# 1_P1.net
KiCad netlist of a schematic drawn in Altium Designer
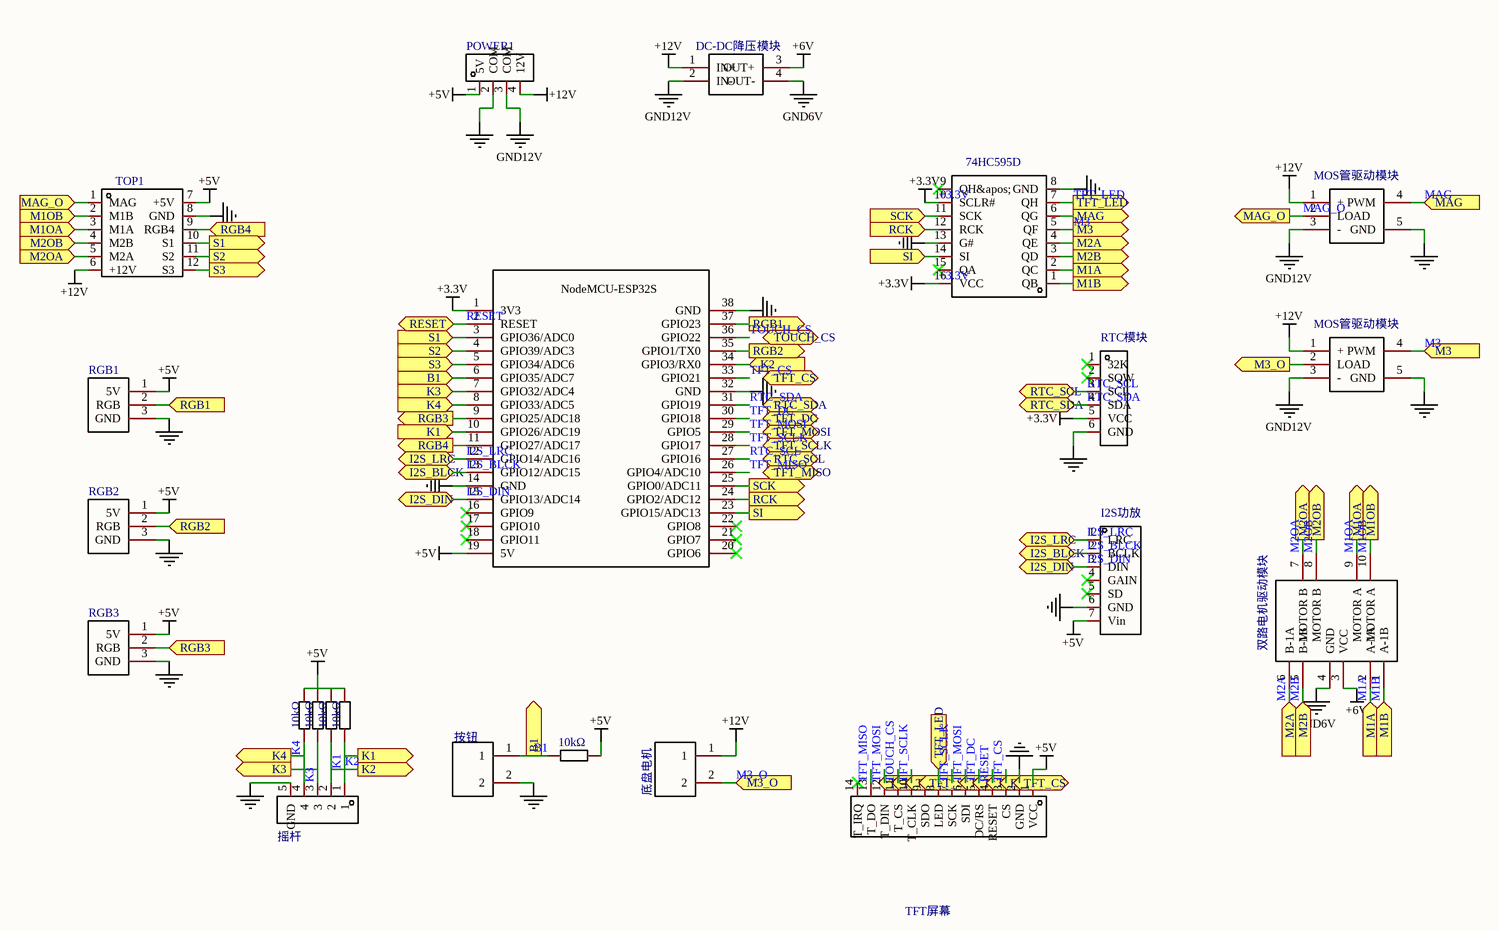
[diagram p0: 1_P1.schdoc]

(export (version "E")
  (design (tool "Eeschema 10.0.6"))
  (components
    (comp (ref "B1")
      (value "按钮")
      (description "系列:PH;连接器类型:接头;触头类型:公形引脚;间距:0.079")
      (fields
        (field (name "NAME") "按钮")
        (field (name "MANUFACTURER") "BOOMELE(博穆精密)")
        (field (name "MANUFACTURER PART") "PH-2A")
      )
      (libsource (lib "altium-import") (part "root_1_按钮_"))
    )
    (comp (ref "H2")
      (value "I2S功放")
      (description "间距:2.54mm;行距:-;触头镀层:-;触头材质:黄铜;安装类型:直插;塑高:-;总孔位数:7;排数:1;")
      (fields
        (field (name "DEVICE") "I2S功放")
        (field (name "MANUFACTURER") "Ckmtw(灿科盟)")
        (field (name "MANUFACTURER PART") "B-2200S07P-A120")
      )
      (libsource (lib "altium-import") (part "root_0_I2S功放_"))
    )
    (comp (ref "KEYPAD1")
      (value "摇杆")
      (description "系列:PH;连接器类型:接头;触头类型:公形引脚;间距:0.079")
      (fields
        (field (name "DEVICE") "摇杆")
        (field (name "MANUFACTURER") "BOOMELE(博穆精密)")
        (field (name "MANUFACTURER PART") "PH-5A")
      )
      (libsource (lib "altium-import") (part "root_3_摇杆_"))
    )
    (comp (ref "M3")
      (value "底盘电机")
      (description "系列:PH;连接器类型:接头;触头类型:公形引脚;间距:0.079")
      (fields
        (field (name "NAME") "底盘电机")
        (field (name "MANUFACTURER") "BOOMELE(博穆精密)")
        (field (name "MANUFACTURER PART") "PH-2A")
      )
      (libsource (lib "altium-import") (part "root_1_按钮_"))
    )
    (comp (ref "P5")
      (value "RTC模块")
      (description "间距:2.54mm;行距:-;触头镀层:-;触头材质:-;安装类型:直插;塑高:-;总孔位数:6;排数:1;")
      (fields
        (field (name "DEVICE") "RTC模块")
        (field (name "MANUFACTURER") "BOOMELE(博穆精密)")
        (field (name "MANUFACTURER PART") "2.54-1*6P母")
      )
      (libsource (lib "altium-import") (part "root_0_RTC模块_"))
    )
    (comp (ref "POWER1")
      (value "开关电源接线柱")
      (fields
        (field (name "MANUFACTURER") "DIBO(地博电子)")
        (field (name "MANUFACTURER PART") "DB125-3.81-4P-GN")
      )
      (libsource (lib "altium-import") (part "root_1_开关电源接线柱_"))
    )
    (comp (ref "R1")
      (value "10kΩ")
      (description "精度:±1%;温度系数:±100ppm/℃;阻值:10kΩ;功率:100mW;最大工作电压:75V;工作温度范围:-55℃~+155℃;")
      (fields (field (name "MANUFACTURER") "YAGEO(国巨)") (field (name "MANUFACTURER PART") "RC0603FR-0710KL"))
      (libsource (lib "altium-import") (part "root_1_RC0603FR-0710KL_"))
    )
    (comp (ref "R2")
      (value "10kΩ")
      (description "精度:±1%;温度系数:±100ppm/℃;阻值:10kΩ;功率:100mW;最大工作电压:75V;工作温度范围:-55℃~+155℃;")
      (fields (field (name "MANUFACTURER") "YAGEO(国巨)") (field (name "MANUFACTURER PART") "RC0603FR-0710KL"))
      (libsource (lib "altium-import") (part "root_1_RC0603FR-0710KL_"))
    )
    (comp (ref "R3")
      (value "10kΩ")
      (description "精度:±1%;温度系数:±100ppm/℃;阻值:10kΩ;功率:100mW;最大工作电压:75V;工作温度范围:-55℃~+155℃;")
      (fields (field (name "MANUFACTURER") "YAGEO(国巨)") (field (name "MANUFACTURER PART") "RC0603FR-0710KL"))
      (libsource (lib "altium-import") (part "root_1_RC0603FR-0710KL_"))
    )
    (comp (ref "R4")
      (value "10kΩ")
      (description "精度:±1%;温度系数:±100ppm/℃;阻值:10kΩ;功率:100mW;最大工作电压:75V;工作温度范围:-55℃~+155℃;")
      (fields (field (name "MANUFACTURER") "YAGEO(国巨)") (field (name "MANUFACTURER PART") "RC0603FR-0710KL"))
      (libsource (lib "altium-import") (part "root_1_RC0603FR-0710KL_"))
    )
    (comp (ref "R5")
      (value "10kΩ")
      (description "精度:±1%;温度系数:±100ppm/℃;阻值:10kΩ;功率:100mW;最大工作电压:75V;工作温度范围:-55℃~+155℃;")
      (fields (field (name "MANUFACTURER") "YAGEO(国巨)") (field (name "MANUFACTURER PART") "RC0603FR-0710KL"))
      (libsource (lib "altium-import") (part "root_0_RC0603FR-0710KL_"))
    )
    (comp (ref "RGB1")
      (value "RGB1")
      (description "系列:PH;连接器类型:接头;触头类型:公形引脚;间距:0.079")
      (fields
        (field (name "NAME") "RGB1")
        (field (name "MANUFACTURER") "BOOMELE(博穆精密)")
        (field (name "MANUFACTURER PART") "PH-3A")
      )
      (libsource (lib "altium-import") (part "root_0_RGB_"))
    )
    (comp (ref "RGB2")
      (value "RGB2")
      (description "系列:PH;连接器类型:接头;触头类型:公形引脚;间距:0.079")
      (fields
        (field (name "NAME") "RGB2")
        (field (name "MANUFACTURER") "BOOMELE(博穆精密)")
        (field (name "MANUFACTURER PART") "PH-3A")
      )
      (libsource (lib "altium-import") (part "root_0_RGB_"))
    )
    (comp (ref "RGB3")
      (value "RGB3")
      (description "系列:PH;连接器类型:接头;触头类型:公形引脚;间距:0.079")
      (fields
        (field (name "NAME") "RGB3")
        (field (name "MANUFACTURER") "BOOMELE(博穆精密)")
        (field (name "MANUFACTURER PART") "PH-3A")
      )
      (libsource (lib "altium-import") (part "root_0_RGB_"))
    )
    (comp (ref "SCREEN1")
      (value "TFT屏幕")
      (fields
        (field (name "DEVICE") "TFT屏幕")
        (field (name "MANUFACTURER") "kinghelm(金航标)")
        (field (name "MANUFACTURER PART") "KH-A2541WV-14P")
      )
      (libsource (lib "altium-import") (part "root_3_TFT屏幕_"))
    )
    (comp (ref "TOP1")
      (value "顶盖")
      (description "系列:PHD;连接器类型:接头;触头类型:公形引脚;间距:0.079")
      (fields (field (name "MANUFACTURER") "BOOMELE(博穆精密)") (field (name "MANUFACTURER PART") "PHD-2*6A"))
      (libsource (lib "altium-import") (part "root_0_顶盖_"))
    )
    (comp (ref "U1") (value "NodeMCU-32S") (libsource (lib "altium-import") (part "root_0_NodeMCU-32S_")))
    (comp (ref "U15")
      (value "74HC595D")
      (description "输出类型:-;元件数:-;每元件位数:-;逻辑电路的归属系列:-;逻辑类型:-;")
      (fields (field (name "DEVICE") "74HC595D") (field (name "MANUFACTURER") "TOSHIBA(东芝)"))
      (libsource (lib "altium-import") (part "root_2_74HC595D_"))
    )
    (comp (ref "U16")
      (value "双路电机驱动模块")
      (fields (field (name "DEVICE") "双路电机驱动模块"))
      (libsource (lib "altium-import") (part "root_1_双路电机驱动模块_"))
    )
    (comp (ref "U17")
      (value "DC-DC降压模块")
      (fields (field (name "SYMBOL") "DC-DC降压模块"))
      (libsource (lib "altium-import") (part "root_0_DC-DC降压模块_"))
    )
    (comp (ref "U18")
      (value "MOS管驱动模块")
      (fields (field (name "DEVICE") "MOS管驱动模块"))
      (libsource (lib "altium-import") (part "root_0_MOS管驱动模块_"))
    )
    (comp (ref "U19")
      (value "MOS管驱动模块")
      (fields (field (name "DEVICE") "MOS管驱动模块"))
      (libsource (lib "altium-import") (part "root_0_MOS管驱动模块_"))
    )
  )
  (nets
    (net (code "1") (name "+3.3V") (class "Default")
      (node (ref "P5") (pin "5") (pinfunction "VCC_5") (pintype "passive"))
      (node (ref "U1") (pin "1") (pinfunction "3V3_1") (pintype "passive"))
      (node (ref "U15") (pin "10") (pinfunction "SCLR#_10") (pintype "passive"))
      (node (ref "U15") (pin "16") (pinfunction "VCC_16") (pintype "passive"))
    )
    (net (code "2") (name "+5V") (class "Default")
      (node (ref "H2") (pin "7") (pinfunction "Vin_7") (pintype "passive"))
      (node (ref "POWER1") (pin "1") (pinfunction "5V_1") (pintype "passive"))
      (node (ref "R1") (pin "2") (pinfunction "2_2") (pintype "passive"))
      (node (ref "R2") (pin "2") (pinfunction "2_2") (pintype "passive"))
      (node (ref "R3") (pin "2") (pinfunction "2_2") (pintype "passive"))
      (node (ref "R4") (pin "2") (pinfunction "2_2") (pintype "passive"))
      (node (ref "R5") (pin "2") (pinfunction "2_2") (pintype "passive"))
      (node (ref "RGB1") (pin "1") (pinfunction "5V_1") (pintype "passive"))
      (node (ref "RGB2") (pin "1") (pinfunction "5V_1") (pintype "passive"))
      (node (ref "RGB3") (pin "1") (pinfunction "5V_1") (pintype "passive"))
      (node (ref "SCREEN1") (pin "1") (pinfunction "VCC_1") (pintype "passive"))
      (node (ref "TOP1") (pin "7") (pinfunction "+5V_7") (pintype "passive"))
      (node (ref "U1") (pin "19") (pinfunction "5V_19") (pintype "passive"))
    )
    (net (code "3") (name "+6V") (class "Default")
      (node (ref "U16") (pin "3") (pinfunction "VCC_3") (pintype "passive"))
      (node (ref "U17") (pin "3") (pinfunction "OUT+_3") (pintype "passive"))
    )
    (net (code "4") (name "+12V") (class "Default")
      (node (ref "M3") (pin "1") (pinfunction "1_1") (pintype "passive"))
      (node (ref "POWER1") (pin "4") (pinfunction "12V_4") (pintype "passive"))
      (node (ref "TOP1") (pin "6") (pinfunction "+12V_6") (pintype "passive"))
      (node (ref "U17") (pin "1") (pinfunction "IN+_1") (pintype "passive"))
      (node (ref "U18") (pin "1") (pinfunction "+_1") (pintype "passive"))
      (node (ref "U19") (pin "1") (pinfunction "+_1") (pintype "passive"))
    )
    (net (code "5") (name "/B1") (class "Default")
      (node (ref "B1") (pin "1") (pinfunction "1_1") (pintype "passive"))
      (node (ref "R5") (pin "1") (pinfunction "1_1") (pintype "passive"))
      (node (ref "U1") (pin "6") (pinfunction "GPIO35/ADC7_6") (pintype "passive"))
    )
    (net (code "6") (name "/I2S_BLCK") (class "Default")
      (node (ref "H2") (pin "2") (pinfunction "BCLK_2") (pintype "passive"))
      (node (ref "U1") (pin "13") (pinfunction "GPIO12/ADC15_13") (pintype "passive"))
    )
    (net (code "7") (name "/I2S_DIN") (class "Default")
      (node (ref "H2") (pin "3") (pinfunction "DIN_3") (pintype "passive"))
      (node (ref "U1") (pin "15") (pinfunction "GPIO13/ADC14_15") (pintype "passive"))
    )
    (net (code "8") (name "/I2S_LRC") (class "Default")
      (node (ref "H2") (pin "1") (pinfunction "LRC_1") (pintype "passive"))
      (node (ref "U1") (pin "12") (pinfunction "GPIO14/ADC16_12") (pintype "passive"))
    )
    (net (code "9") (name "/K1") (class "Default")
      (node (ref "KEYPAD1") (pin "1") (pinfunction "1_1") (pintype "passive"))
      (node (ref "KEYPAD1") (pin "2") (pinfunction "2_2") (pintype "passive"))
      (node (ref "R3") (pin "1") (pinfunction "1_1") (pintype "passive"))
      (node (ref "R4") (pin "1") (pinfunction "1_1") (pintype "passive"))
      (node (ref "U1") (pin "10") (pinfunction "GPIO26/ADC19_10") (pintype "passive"))
      (node (ref "U1") (pin "34") (pinfunction "GPIO3/RX0_34") (pintype "passive"))
    )
    (net (code "10") (name "/K3") (class "Default")
      (node (ref "KEYPAD1") (pin "3") (pinfunction "3_3") (pintype "passive"))
      (node (ref "R2") (pin "1") (pinfunction "1_1") (pintype "passive"))
      (node (ref "U1") (pin "7") (pinfunction "GPIO32/ADC4_7") (pintype "passive"))
    )
    (net (code "11") (name "/K4") (class "Default")
      (node (ref "KEYPAD1") (pin "4") (pinfunction "4_4") (pintype "passive"))
      (node (ref "R1") (pin "1") (pinfunction "1_1") (pintype "passive"))
      (node (ref "U1") (pin "8") (pinfunction "GPIO33/ADC5_8") (pintype "passive"))
    )
    (net (code "12") (name "/M1A") (class "Default")
      (node (ref "U15") (pin "2") (pinfunction "QC_2") (pintype "passive"))
      (node (ref "U16") (pin "2") (pinfunction "A-1A_2") (pintype "passive"))
    )
    (net (code "13") (name "/M1B") (class "Default")
      (node (ref "U15") (pin "1") (pinfunction "QB_1") (pintype "passive"))
      (node (ref "U16") (pin "1") (pinfunction "A-1B_1") (pintype "passive"))
    )
    (net (code "14") (name "/M1OA") (class "Default")
      (node (ref "TOP1") (pin "3") (pinfunction "M1A_3") (pintype "passive"))
      (node (ref "U16") (pin "9") (pinfunction "MOTOR_A_9") (pintype "passive"))
    )
    (net (code "15") (name "/M1OB") (class "Default")
      (node (ref "TOP1") (pin "2") (pinfunction "M1B_2") (pintype "passive"))
      (node (ref "U16") (pin "10") (pinfunction "MOTOR_A_10") (pintype "passive"))
    )
    (net (code "16") (name "/M2A") (class "Default")
      (node (ref "U15") (pin "4") (pinfunction "QE_4") (pintype "passive"))
      (node (ref "U16") (pin "6") (pinfunction "B-1A_6") (pintype "passive"))
    )
    (net (code "17") (name "/M2B") (class "Default")
      (node (ref "U15") (pin "3") (pinfunction "QD_3") (pintype "passive"))
      (node (ref "U16") (pin "5") (pinfunction "B-1B_5") (pintype "passive"))
    )
    (net (code "18") (name "/M2OA") (class "Default")
      (node (ref "TOP1") (pin "5") (pinfunction "M2A_5") (pintype "passive"))
      (node (ref "U16") (pin "7") (pinfunction "MOTOR_B_7") (pintype "passive"))
    )
    (net (code "19") (name "/M2OB") (class "Default")
      (node (ref "TOP1") (pin "4") (pinfunction "M2B_4") (pintype "passive"))
      (node (ref "U16") (pin "8") (pinfunction "MOTOR_B_8") (pintype "passive"))
    )
    (net (code "20") (name "/M3") (class "Default")
      (node (ref "U15") (pin "5") (pinfunction "QF_5") (pintype "passive"))
      (node (ref "U19") (pin "4") (pinfunction "PWM_4") (pintype "passive"))
    )
    (net (code "21") (name "/M3_O") (class "Default")
      (node (ref "M3") (pin "2") (pinfunction "2_2") (pintype "passive"))
      (node (ref "U19") (pin "2") (pinfunction "LOAD_2") (pintype "passive"))
    )
    (net (code "22") (name "/MAG") (class "Default")
      (node (ref "U15") (pin "6") (pinfunction "QG_6") (pintype "passive"))
      (node (ref "U18") (pin "4") (pinfunction "PWM_4") (pintype "passive"))
    )
    (net (code "23") (name "/MAG_O") (class "Default")
      (node (ref "TOP1") (pin "1") (pinfunction "MAG_1") (pintype "passive"))
      (node (ref "U18") (pin "2") (pinfunction "LOAD_2") (pintype "passive"))
    )
    (net (code "24") (name "/RCK") (class "Default")
      (node (ref "U1") (pin "24") (pinfunction "GPIO2/ADC12_24") (pintype "passive"))
      (node (ref "U15") (pin "12") (pinfunction "RCK_12") (pintype "passive"))
    )
    (net (code "25") (name "/RESET") (class "Default")
      (node (ref "SCREEN1") (pin "4") (pinfunction "RESET_4") (pintype "passive"))
      (node (ref "U1") (pin "2") (pinfunction "RESET_2") (pintype "passive"))
    )
    (net (code "26") (name "/RGB1") (class "Default")
      (node (ref "RGB1") (pin "2") (pinfunction "RGB_2") (pintype "passive"))
      (node (ref "U1") (pin "37") (pinfunction "GPIO23_37") (pintype "passive"))
    )
    (net (code "27") (name "/RGB2") (class "Default")
      (node (ref "RGB2") (pin "2") (pinfunction "RGB_2") (pintype "passive"))
      (node (ref "U1") (pin "35") (pinfunction "GPIO1/TX0_35") (pintype "passive"))
    )
    (net (code "28") (name "/RGB3") (class "Default")
      (node (ref "RGB3") (pin "2") (pinfunction "RGB_2") (pintype "passive"))
      (node (ref "U1") (pin "9") (pinfunction "GPIO25/ADC18_9") (pintype "passive"))
    )
    (net (code "29") (name "/RGB4") (class "Default")
      (node (ref "TOP1") (pin "9") (pinfunction "RGB4_9") (pintype "passive"))
      (node (ref "U1") (pin "11") (pinfunction "GPIO27/ADC17_11") (pintype "passive"))
    )
    (net (code "30") (name "/RTC_SCL") (class "Default")
      (node (ref "P5") (pin "3") (pinfunction "SCL_3") (pintype "passive"))
      (node (ref "U1") (pin "27") (pinfunction "GPIO16_27") (pintype "passive"))
    )
    (net (code "31") (name "/RTC_SDA") (class "Default")
      (node (ref "P5") (pin "4") (pinfunction "SDA_4") (pintype "passive"))
      (node (ref "U1") (pin "31") (pinfunction "GPIO19_31") (pintype "passive"))
    )
    (net (code "32") (name "/S1") (class "Default")
      (node (ref "TOP1") (pin "10") (pinfunction "S1_10") (pintype "passive"))
      (node (ref "U1") (pin "3") (pinfunction "GPIO36/ADC0_3") (pintype "passive"))
    )
    (net (code "33") (name "/S2") (class "Default")
      (node (ref "TOP1") (pin "11") (pinfunction "S2_11") (pintype "passive"))
      (node (ref "U1") (pin "4") (pinfunction "GPIO39/ADC3_4") (pintype "passive"))
    )
    (net (code "34") (name "/S3") (class "Default")
      (node (ref "TOP1") (pin "12") (pinfunction "S3_12") (pintype "passive"))
      (node (ref "U1") (pin "5") (pinfunction "GPIO34/ADC6_5") (pintype "passive"))
    )
    (net (code "35") (name "/SCK") (class "Default")
      (node (ref "U1") (pin "25") (pinfunction "GPIO0/ADC11_25") (pintype "passive"))
      (node (ref "U15") (pin "11") (pinfunction "SCK_11") (pintype "passive"))
    )
    (net (code "36") (name "/SI") (class "Default")
      (node (ref "U1") (pin "23") (pinfunction "GPIO15/ADC13_23") (pintype "passive"))
      (node (ref "U15") (pin "14") (pinfunction "SI_14") (pintype "passive"))
    )
    (net (code "37") (name "/TFT_CS") (class "Default")
      (node (ref "SCREEN1") (pin "3") (pinfunction "CS_3") (pintype "passive"))
      (node (ref "U1") (pin "33") (pinfunction "GPIO21_33") (pintype "passive"))
    )
    (net (code "38") (name "/TFT_DC") (class "Default")
      (node (ref "SCREEN1") (pin "5") (pinfunction "DC/RS_5") (pintype "passive"))
      (node (ref "U1") (pin "30") (pinfunction "GPIO18_30") (pintype "passive"))
    )
    (net (code "39") (name "/TFT_LED") (class "Default")
      (node (ref "SCREEN1") (pin "8") (pinfunction "LED_8") (pintype "passive"))
      (node (ref "U15") (pin "7") (pinfunction "QH_7") (pintype "passive"))
    )
    (net (code "40") (name "/TFT_MISO") (class "Default")
      (node (ref "SCREEN1") (pin "13") (pinfunction "T_DO_13") (pintype "passive"))
      (node (ref "U1") (pin "26") (pinfunction "GPIO4/ADC10_26") (pintype "passive"))
    )
    (net (code "41") (name "/TFT_MOSI") (class "Default")
      (node (ref "SCREEN1") (pin "12") (pinfunction "T_DIN_12") (pintype "passive"))
      (node (ref "SCREEN1") (pin "6") (pinfunction "SDI_6") (pintype "passive"))
      (node (ref "U1") (pin "29") (pinfunction "GPIO5_29") (pintype "passive"))
    )
    (net (code "42") (name "/TFT_SCLK") (class "Default")
      (node (ref "SCREEN1") (pin "10") (pinfunction "T_CLK_10") (pintype "passive"))
      (node (ref "SCREEN1") (pin "7") (pinfunction "SCK_7") (pintype "passive"))
      (node (ref "U1") (pin "28") (pinfunction "GPIO17_28") (pintype "passive"))
    )
    (net (code "43") (name "/TOUCH_CS") (class "Default")
      (node (ref "SCREEN1") (pin "11") (pinfunction "T_CS_11") (pintype "passive"))
      (node (ref "U1") (pin "36") (pinfunction "GPIO22_36") (pintype "passive"))
    )
    (net (code "44") (name "GND") (class "Default")
      (node (ref "B1") (pin "2") (pinfunction "2_2") (pintype "passive"))
      (node (ref "H2") (pin "6") (pinfunction "GND_6") (pintype "passive"))
      (node (ref "KEYPAD1") (pin "5") (pinfunction "GND_5") (pintype "passive"))
      (node (ref "P5") (pin "6") (pinfunction "GND_6") (pintype "passive"))
      (node (ref "POWER1") (pin "2") (pinfunction "COM_2") (pintype "passive"))
      (node (ref "RGB1") (pin "3") (pinfunction "GND_3") (pintype "passive"))
      (node (ref "RGB2") (pin "3") (pinfunction "GND_3") (pintype "passive"))
      (node (ref "RGB3") (pin "3") (pinfunction "GND_3") (pintype "passive"))
      (node (ref "SCREEN1") (pin "2") (pinfunction "GND_2") (pintype "passive"))
      (node (ref "TOP1") (pin "8") (pinfunction "GND_8") (pintype "passive"))
      (node (ref "U1") (pin "14") (pinfunction "GND_14") (pintype "passive"))
      (node (ref "U1") (pin "32") (pinfunction "GND_32") (pintype "passive"))
      (node (ref "U1") (pin "38") (pinfunction "GND_38") (pintype "passive"))
      (node (ref "U15") (pin "13") (pinfunction "G#_13") (pintype "passive"))
      (node (ref "U15") (pin "8") (pinfunction "GND_8") (pintype "passive"))
      (node (ref "U18") (pin "5") (pinfunction "GND_5") (pintype "passive"))
      (node (ref "U19") (pin "5") (pinfunction "GND_5") (pintype "passive"))
    )
    (net (code "45") (name "GND6V") (class "Default")
      (node (ref "U16") (pin "4") (pinfunction "GND_4") (pintype "passive"))
      (node (ref "U17") (pin "4") (pinfunction "OUT-_4") (pintype "passive"))
    )
    (net (code "46") (name "GND12V") (class "Default")
      (node (ref "POWER1") (pin "3") (pinfunction "COM_3") (pintype "passive"))
      (node (ref "U17") (pin "2") (pinfunction "IN-_2") (pintype "passive"))
      (node (ref "U18") (pin "3") (pinfunction "-_3") (pintype "passive"))
      (node (ref "U19") (pin "3") (pinfunction "-_3") (pintype "passive"))
    )
    (net (code "47") (name "unconnected-(H2-GAIN-Pad4)") (class "Default")
      (node (ref "H2") (pin "4") (pinfunction "GAIN_4") (pintype "passive+no_connect"))
    )
    (net (code "48") (name "unconnected-(H2-SD-Pad5)") (class "Default")
      (node (ref "H2") (pin "5") (pinfunction "SD_5") (pintype "passive+no_connect"))
    )
    (net (code "49") (name "unconnected-(P5-32K-Pad1)") (class "Default")
      (node (ref "P5") (pin "1") (pinfunction "32K_1") (pintype "passive+no_connect"))
    )
    (net (code "50") (name "unconnected-(P5-SQW-Pad2)") (class "Default")
      (node (ref "P5") (pin "2") (pinfunction "SQW_2") (pintype "passive+no_connect"))
    )
    (net (code "51") (name "unconnected-(SCREEN1-SDO-Pad9)") (class "Default")
      (node (ref "SCREEN1") (pin "9") (pinfunction "SDO_9") (pintype "passive+no_connect"))
    )
    (net (code "52") (name "unconnected-(SCREEN1-T_IRQ-Pad14)") (class "Default")
      (node (ref "SCREEN1") (pin "14") (pinfunction "T_IRQ_14") (pintype "passive+no_connect"))
    )
    (net (code "53") (name "unconnected-(U1-GPIO6-Pad20)") (class "Default")
      (node (ref "U1") (pin "20") (pinfunction "GPIO6_20") (pintype "passive+no_connect"))
    )
    (net (code "54") (name "unconnected-(U1-GPIO7-Pad21)") (class "Default")
      (node (ref "U1") (pin "21") (pinfunction "GPIO7_21") (pintype "passive+no_connect"))
    )
    (net (code "55") (name "unconnected-(U1-GPIO8-Pad22)") (class "Default")
      (node (ref "U1") (pin "22") (pinfunction "GPIO8_22") (pintype "passive+no_connect"))
    )
    (net (code "56") (name "unconnected-(U1-GPIO9-Pad16)") (class "Default")
      (node (ref "U1") (pin "16") (pinfunction "GPIO9_16") (pintype "passive+no_connect"))
    )
    (net (code "57") (name "unconnected-(U1-GPIO10-Pad17)") (class "Default")
      (node (ref "U1") (pin "17") (pinfunction "GPIO10_17") (pintype "passive+no_connect"))
    )
    (net (code "58") (name "unconnected-(U1-GPIO11-Pad18)") (class "Default")
      (node (ref "U1") (pin "18") (pinfunction "GPIO11_18") (pintype "passive+no_connect"))
    )
    (net (code "59") (name "unconnected-(U15-QA-Pad15)") (class "Default")
      (node (ref "U15") (pin "15") (pinfunction "QA_15") (pintype "passive+no_connect"))
    )
    (net (code "60") (name "unconnected-(U15-QH&apos;-Pad9)") (class "Default")
      (node (ref "U15") (pin "9") (pinfunction "QH&apos;_9") (pintype "passive+no_connect"))
    )
  )
)
